# power_mux-v3.net
KiCad netlist of a schematic drawn in EAGLE
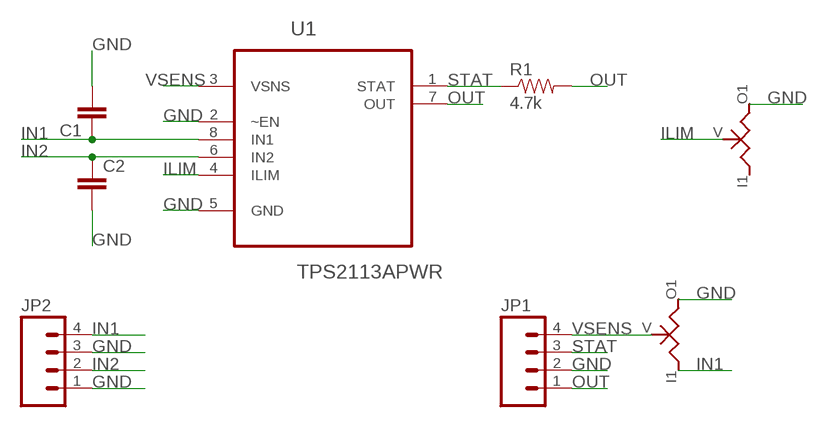
[diagram p0: schematic, sheet 1]

(export (version "E")
  (design (tool "Eeschema 10.0.6"))
  (components
    (comp (ref "C1")
      (value "CAP0805")
      (footprint "eagle-import:0805")
      (libsource (lib "eagle-import") (part "CAP0805"))
    )
    (comp (ref "C2")
      (value "CAP0805")
      (footprint "eagle-import:0805")
      (libsource (lib "eagle-import") (part "CAP0805"))
    )
    (comp (ref "JP1")
      (value "M04PTH")
      (footprint "eagle-import:1X04")
      (libsource (lib "eagle-import") (part "M04PTH"))
    )
    (comp (ref "JP2")
      (value "M04PTH")
      (footprint "eagle-import:1X04")
      (libsource (lib "eagle-import") (part "M04PTH"))
    )
    (comp (ref "R1")
      (value "4.7k")
      (footprint "eagle-import:0805")
      (libsource (lib "eagle-import") (part "RESISTOR0805-RES"))
    )
    (comp (ref "U$1")
      (value "TC33X-2")
      (footprint "eagle-import:TC33X-2")
      (libsource (lib "eagle-import") (part "TC33X-2"))
    )
    (comp (ref "U$2")
      (value "TC33X-2")
      (footprint "eagle-import:TC33X-2")
      (libsource (lib "eagle-import") (part "TC33X-2"))
    )
    (comp (ref "U1")
      (value "TPS2113APWR")
      (footprint "eagle-import:SOP65P640X120-8N")
      (libsource (lib "eagle-import") (part "TPS2113APWR"))
    )
  )
  (nets
    (net (code "1") (name "/GND") (class "Default")
      (node (ref "C1") (pin "2") (pinfunction "2_2") (pintype "passive"))
      (node (ref "C2") (pin "2") (pinfunction "2_2") (pintype "passive"))
      (node (ref "JP1") (pin "2") (pinfunction "2_2") (pintype "passive"))
      (node (ref "JP2") (pin "1") (pinfunction "1_1") (pintype "passive"))
      (node (ref "JP2") (pin "3") (pinfunction "3_3") (pintype "passive"))
      (node (ref "U$1") (pin "O1") (pinfunction "OUT_O1") (pintype "output"))
      (node (ref "U$2") (pin "O1") (pinfunction "OUT_O1") (pintype "output"))
      (node (ref "U1") (pin "2") (pinfunction "~{EN}_2") (pintype "input"))
      (node (ref "U1") (pin "5") (pinfunction "GND_5") (pintype "passive"))
    )
    (net (code "2") (name "/ILIM") (class "Default")
      (node (ref "U$2") (pin "V") (pinfunction "VAR_V") (pintype "output"))
      (node (ref "U1") (pin "4") (pinfunction "ILIM_4") (pintype "input"))
    )
    (net (code "3") (name "/IN1") (class "Default")
      (node (ref "C1") (pin "1") (pinfunction "1_1") (pintype "passive"))
      (node (ref "JP2") (pin "4") (pinfunction "4_4") (pintype "passive"))
      (node (ref "U$1") (pin "I1") (pinfunction "IN_I1") (pintype "input"))
      (node (ref "U1") (pin "8") (pinfunction "IN1_8") (pintype "input"))
    )
    (net (code "4") (name "/IN2") (class "Default")
      (node (ref "C2") (pin "1") (pinfunction "1_1") (pintype "passive"))
      (node (ref "JP2") (pin "2") (pinfunction "2_2") (pintype "passive"))
      (node (ref "U1") (pin "6") (pinfunction "IN2_6") (pintype "input"))
    )
    (net (code "5") (name "/OUT") (class "Default")
      (node (ref "JP1") (pin "1") (pinfunction "1_1") (pintype "passive"))
      (node (ref "R1") (pin "2") (pinfunction "2_2") (pintype "passive"))
      (node (ref "U1") (pin "7") (pinfunction "OUT_7") (pintype "output"))
    )
    (net (code "6") (name "/STAT") (class "Default")
      (node (ref "JP1") (pin "3") (pinfunction "3_3") (pintype "passive"))
      (node (ref "R1") (pin "1") (pinfunction "1_1") (pintype "passive"))
      (node (ref "U1") (pin "1") (pinfunction "STAT_1") (pintype "output"))
    )
    (net (code "7") (name "/VSENS") (class "Default")
      (node (ref "JP1") (pin "4") (pinfunction "4_4") (pintype "passive"))
      (node (ref "U$1") (pin "V") (pinfunction "VAR_V") (pintype "output"))
      (node (ref "U1") (pin "3") (pinfunction "VSNS_3") (pintype "power_in"))
    )
    (net (code "8") (name "unconnected-(U$2-IN-PadI1)") (class "Default")
      (node (ref "U$2") (pin "I1") (pinfunction "IN_I1") (pintype "input"))
    )
  )
)
